# M12-Signalinverter.net
KiCad netlist of a schematic drawn in EAGLE
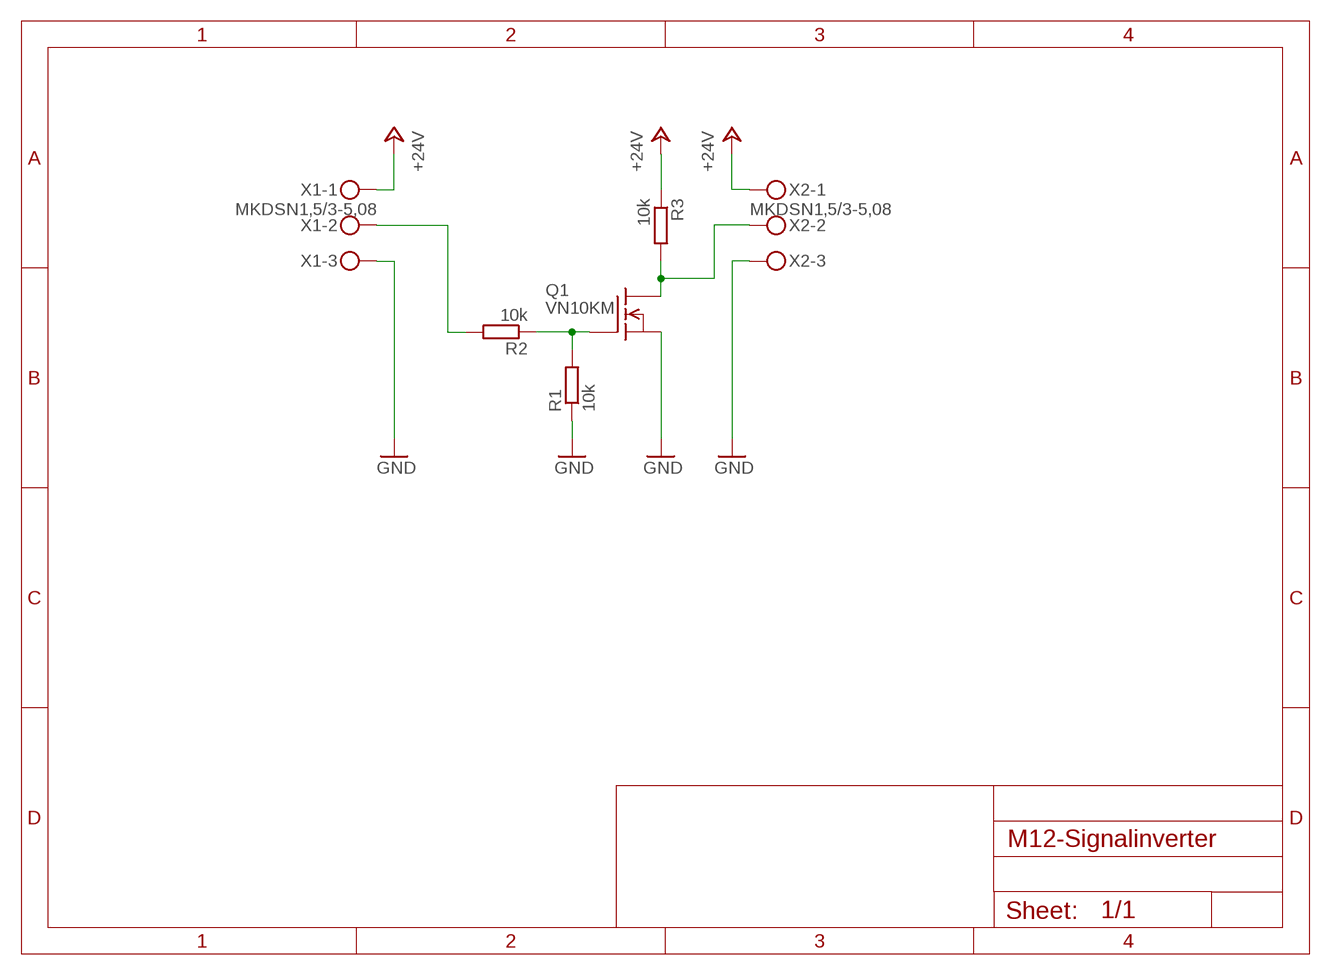
[diagram p0: schematic, sheet 1]

(export (version "E")
  (design (tool "Eeschema 10.0.6"))
  (components
    (comp (ref "Q1")
      (value "VN10KM")
      (footprint "eagle-import:TO237")
      (libsource (lib "eagle-import") (part "VN10KM"))
    )
    (comp (ref "R1")
      (value "10k")
      (footprint "eagle-import:0207_7")
      (libsource (lib "eagle-import") (part "R-EU_0207/7"))
    )
    (comp (ref "R2")
      (value "10k")
      (footprint "eagle-import:0207_7")
      (libsource (lib "eagle-import") (part "R-EU_0207/7"))
    )
    (comp (ref "R3")
      (value "10k")
      (footprint "eagle-import:0207_7")
      (libsource (lib "eagle-import") (part "R-EU_0207/7"))
    )
    (comp (ref "X1")
      (value "MKDSN1,5/3-5,08")
      (footprint "eagle-import:MKDSN1,5_3-5,08")
      (libsource (lib "eagle-import") (part "MKDSN1,5/3-5,08"))
    )
    (comp (ref "X2")
      (value "MKDSN1,5/3-5,08")
      (footprint "eagle-import:MKDSN1,5_3-5,08")
      (libsource (lib "eagle-import") (part "MKDSN1,5/3-5,08"))
    )
  )
  (nets
    (net (code "1") (name "+24V") (class "Default")
      (node (ref "R3") (pin "1") (pinfunction "1_1") (pintype "passive"))
      (node (ref "X1") (pin "1") (pinfunction "KL_1") (pintype "passive"))
      (node (ref "X2") (pin "1") (pinfunction "KL_1") (pintype "passive"))
    )
    (net (code "2") (name "GND") (class "Default")
      (node (ref "Q1") (pin "3") (pinfunction "S_3") (pintype "passive"))
      (node (ref "R1") (pin "1") (pinfunction "1_1") (pintype "passive"))
      (node (ref "X1") (pin "3") (pinfunction "KL_3") (pintype "passive"))
      (node (ref "X2") (pin "3") (pinfunction "KL_3") (pintype "passive"))
    )
    (net (code "3") (name "Net-(Q1-D)") (class "Default")
      (node (ref "Q1") (pin "1") (pinfunction "D_1") (pintype "passive"))
      (node (ref "R3") (pin "2") (pinfunction "2_2") (pintype "passive"))
      (node (ref "X2") (pin "2") (pinfunction "KL_2") (pintype "passive"))
    )
    (net (code "4") (name "Net-(Q1-G)") (class "Default")
      (node (ref "Q1") (pin "2") (pinfunction "G_2") (pintype "passive"))
      (node (ref "R1") (pin "2") (pinfunction "2_2") (pintype "passive"))
      (node (ref "R2") (pin "1") (pinfunction "1_1") (pintype "passive"))
    )
    (net (code "5") (name "Net-(X1B-KL)") (class "Default")
      (node (ref "R2") (pin "2") (pinfunction "2_2") (pintype "passive"))
      (node (ref "X1") (pin "2") (pinfunction "KL_2") (pintype "passive"))
    )
  )
)
